# ESP32_BDB-2.net
KiCad netlist of a schematic drawn in Altium Designer
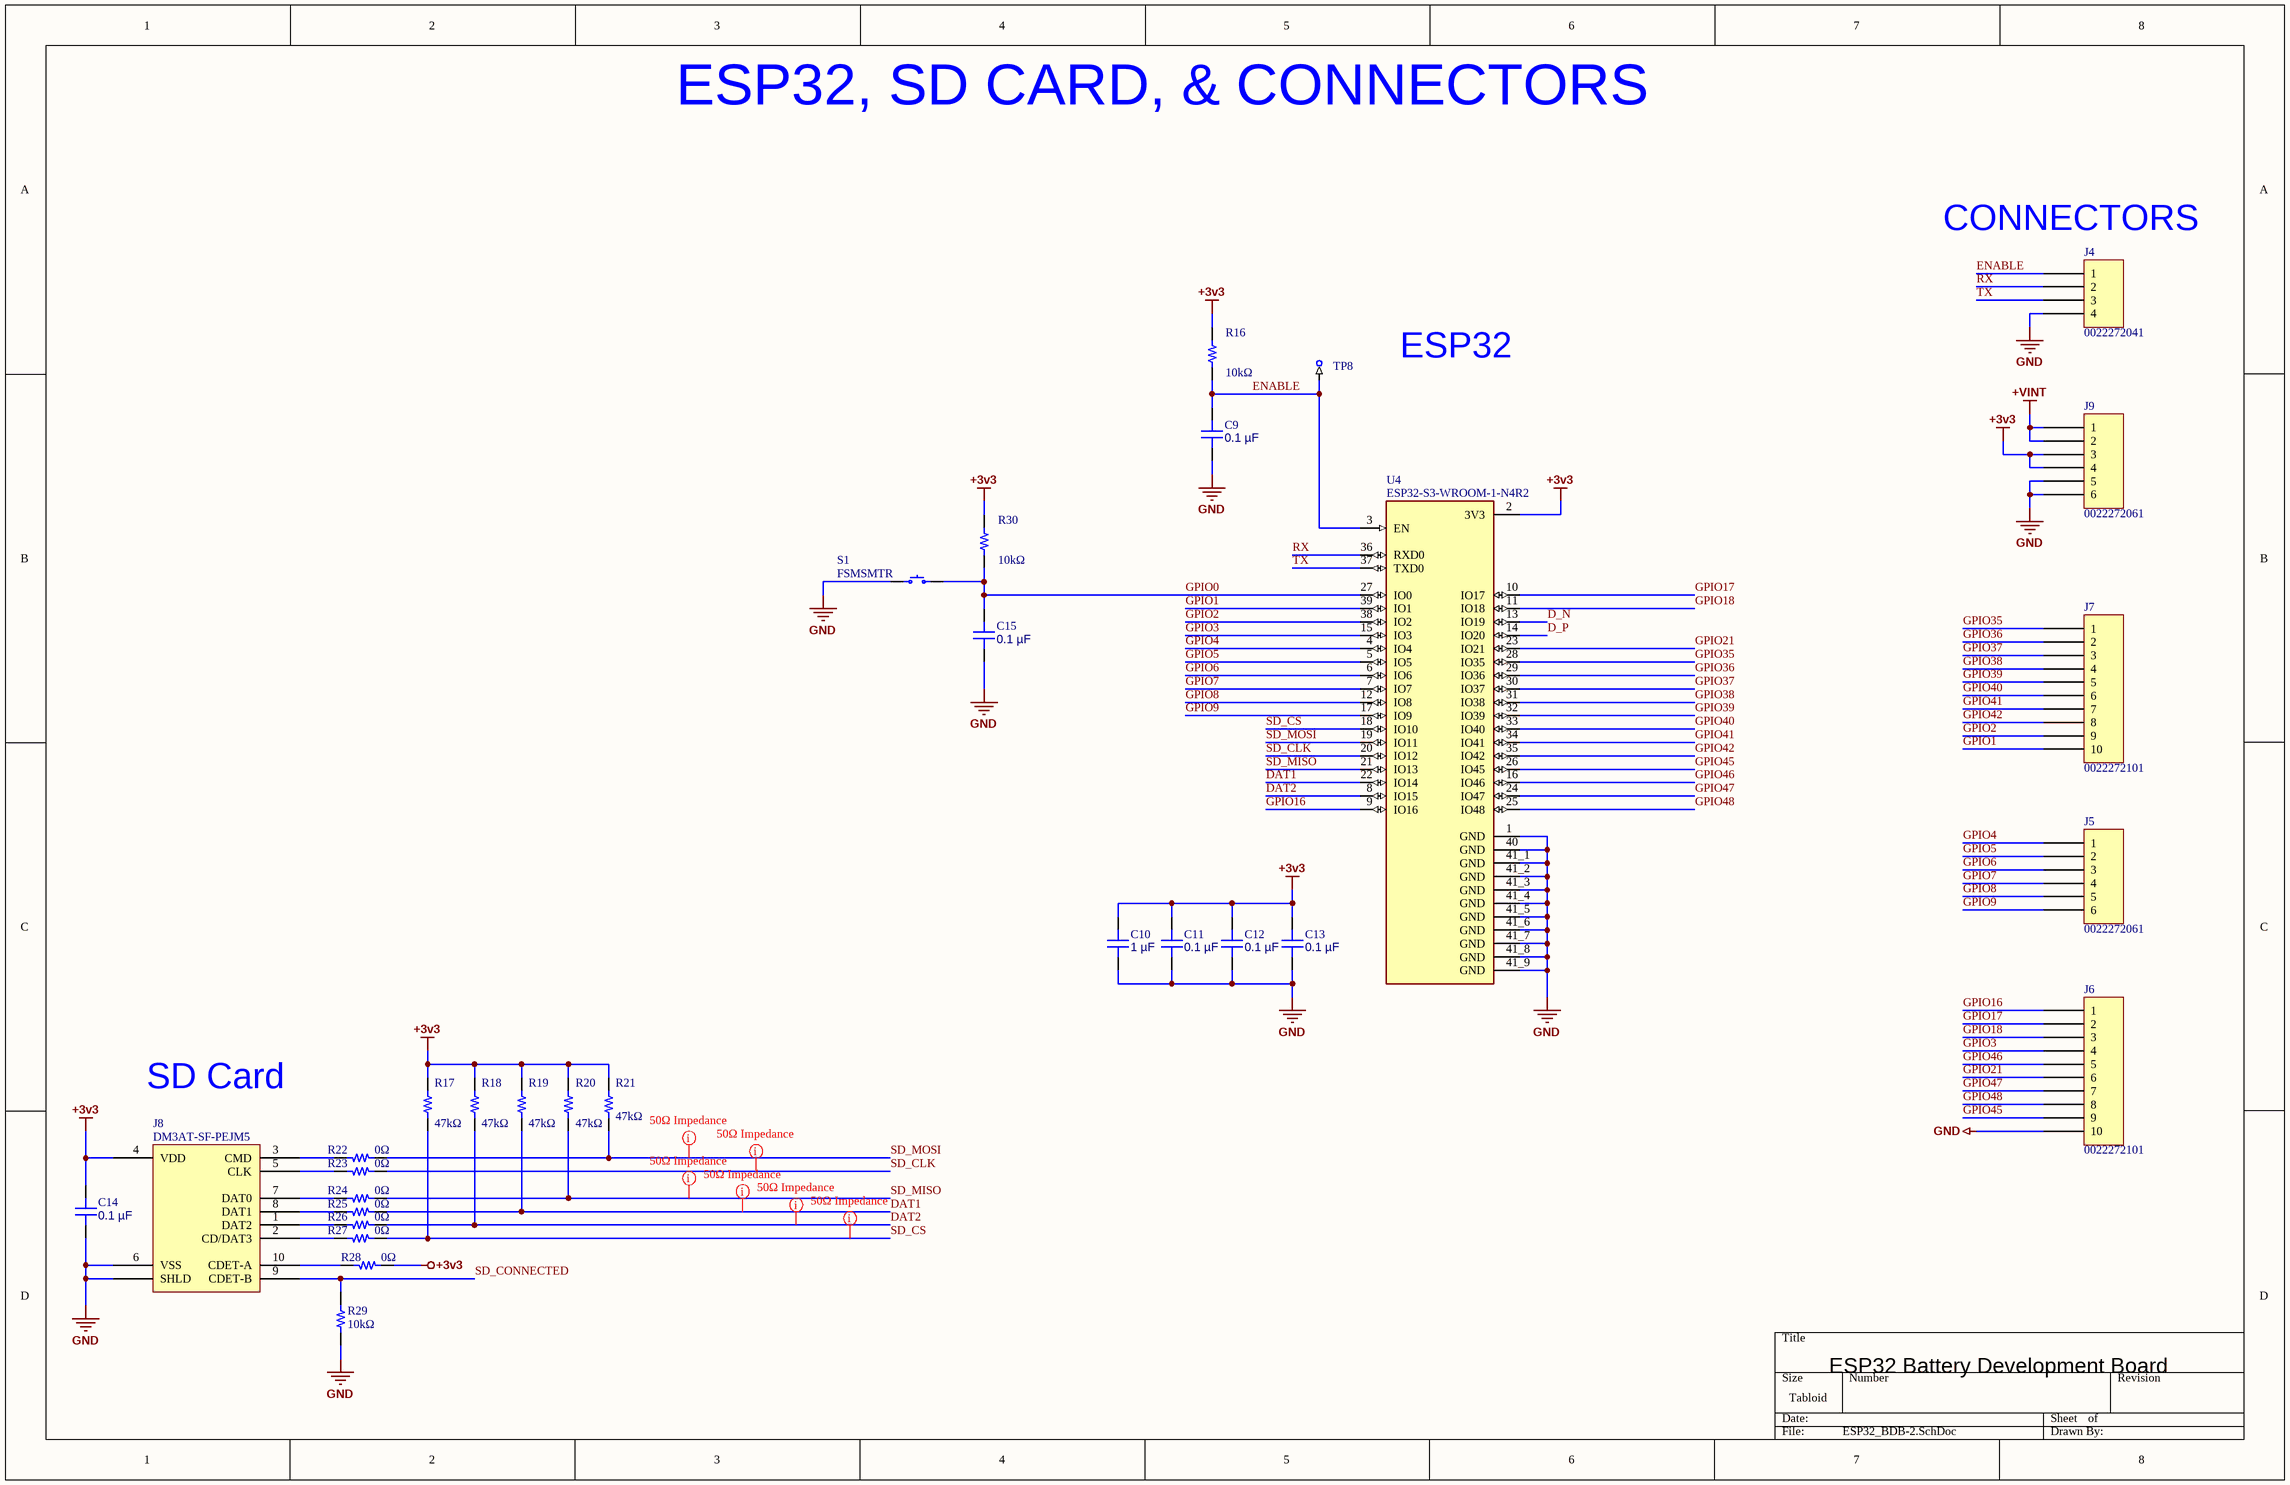
[diagram p0: ESP32_BDB-2.SchDoc]

(export (version "E")
  (design (tool "Eeschema 10.0.6"))
  (components
    (comp (ref "C9")
      (value "0.1 µF")
      (footprint "CAP 0603_1608")
      (description "CAP CER 0.1UF 50V X7R 0603")
      (fields
        (field (name "PART NUMBER") "C0603C104K5RAC7411")
        (field (name "CAPACITANCE") "0.1 µF")
        (field (name "MANUFACTURER") "KEMET")
      )
      (libsource (lib "Celestial Altium Library - altium_library") (part "Capacitor"))
    )
    (comp (ref "C10")
      (value "1 µF")
      (footprint "CAP 0603_1608")
      (description "CAP CER 1UF 10V X7R 0603")
      (fields
        (field (name "PART NUMBER") "CC0603KRX7R6BB105")
        (field (name "CAPACITANCE") "1 µF")
        (field (name "MANUFACTURER") "Yageo")
      )
      (libsource (lib "Celestial Altium Library - altium_library") (part "Capacitor"))
    )
    (comp (ref "C11")
      (value "0.1 µF")
      (footprint "CAP 0603_1608")
      (description "CAP CER 0.1UF 50V X7R 0603")
      (fields
        (field (name "PART NUMBER") "C0603C104K5RAC7411")
        (field (name "CAPACITANCE") "0.1 µF")
        (field (name "MANUFACTURER") "KEMET")
      )
      (libsource (lib "Celestial Altium Library - altium_library") (part "Capacitor"))
    )
    (comp (ref "C12")
      (value "0.1 µF")
      (footprint "CAP 0603_1608")
      (description "CAP CER 0.1UF 50V X7R 0603")
      (fields
        (field (name "PART NUMBER") "C0603C104K5RAC7411")
        (field (name "CAPACITANCE") "0.1 µF")
        (field (name "MANUFACTURER") "KEMET")
      )
      (libsource (lib "Celestial Altium Library - altium_library") (part "Capacitor"))
    )
    (comp (ref "C13")
      (value "0.1 µF")
      (footprint "CAP 0603_1608")
      (description "CAP CER 0.1UF 50V X7R 0603")
      (fields
        (field (name "PART NUMBER") "C0603C104K5RAC7411")
        (field (name "CAPACITANCE") "0.1 µF")
        (field (name "MANUFACTURER") "KEMET")
      )
      (libsource (lib "Celestial Altium Library - altium_library") (part "Capacitor"))
    )
    (comp (ref "C14")
      (value "0.1 µF")
      (footprint "CAP 0603_1608")
      (description "CAP CER 0.1UF 50V X7R 0603")
      (fields
        (field (name "PART NUMBER") "C0603C104K5RAC7411")
        (field (name "CAPACITANCE") "0.1 µF")
        (field (name "MANUFACTURER") "KEMET")
      )
      (libsource (lib "Celestial Altium Library - altium_library") (part "Capacitor"))
    )
    (comp (ref "C15")
      (value "0.1 µF")
      (footprint "CAP 0603_1608")
      (description "CAP CER 0.1UF 50V X7R 0603")
      (fields
        (field (name "PART NUMBER") "C0603C104K5RAC7411")
        (field (name "CAPACITANCE") "0.1 µF")
        (field (name "MANUFACTURER") "KEMET")
      )
      (libsource (lib "Celestial Altium Library - altium_library") (part "Capacitor"))
    )
    (comp (ref "J4")
      (value "0022272041")
      (footprint "MOLEX KK 0022272041")
      (description "CONN HEADER VERT 4POS 2.54MM")
      (fields (field (name "MANUFACTURER") "Molex"))
      (libsource (lib "Celestial Altium Library - altium_library") (part "4 Pin"))
    )
    (comp (ref "J5")
      (value "0022272061")
      (footprint "MOLEX KK 0022272061")
      (description "CONN HEADER VERT 6POS 2.54MM")
      (fields (field (name "MANUFACTURER") "Molex"))
      (libsource (lib "Celestial Altium Library - altium_library") (part "6 Pin"))
    )
    (comp (ref "J6")
      (value "0022272101")
      (footprint "MOLEX KK 0022272101")
      (description "CONN HEADER VERT 10POS 2.54MM")
      (fields (field (name "MANUFACTURER") "Molex"))
      (libsource (lib "Celestial Altium Library - altium_library") (part "10 Pin"))
    )
    (comp (ref "J7")
      (value "0022272101")
      (footprint "MOLEX KK 0022272101")
      (description "CONN HEADER VERT 10POS 2.54MM")
      (fields (field (name "MANUFACTURER") "Molex"))
      (libsource (lib "Celestial Altium Library - altium_library") (part "10 Pin"))
    )
    (comp (ref "J8")
      (value "DM3AT-SF-PEJM5")
      (footprint "HIROSE DM3AT-SF-PEJM5")
      (description "CONN MICRO SD CARD PUSH-PUSH R/A")
      (fields (field (name "MANUFACTURER") "Hirose Electric Co Ltd"))
      (libsource (lib "Celestial Altium Library - altium_library") (part "Hirose DM3 MicroSD"))
    )
    (comp (ref "J9")
      (value "0022272061")
      (footprint "MOLEX KK 0022272061")
      (description "CONN HEADER VERT 6POS 2.54MM")
      (fields (field (name "MANUFACTURER") "Molex"))
      (libsource (lib "Celestial Altium Library - altium_library") (part "6 Pin"))
    )
    (comp (ref "R16")
      (value "10kΩ")
      (footprint "RES 0603_1608")
      (description "RES SMD 10K OHM 1% 1/10W 0603")
      (fields (field (name "PART NUMBER") "AA0603FR-0710KL") (field (name "MANUFACTURER") "Yageo"))
      (libsource (lib "Celestial Altium Library - altium_library") (part "Resistor"))
    )
    (comp (ref "R17")
      (value "47kΩ")
      (footprint "RES 0603_1608")
      (description "RES SMD 47K OHM 1% 1/10W 0603")
      (fields (field (name "PART NUMBER") "AC0603FR-0747KL") (field (name "MANUFACTURER") "Yageo"))
      (libsource (lib "Celestial Altium Library - altium_library") (part "Resistor"))
    )
    (comp (ref "R18")
      (value "47kΩ")
      (footprint "RES 0603_1608")
      (description "RES SMD 47K OHM 1% 1/10W 0603")
      (fields (field (name "PART NUMBER") "AC0603FR-0747KL") (field (name "MANUFACTURER") "Yageo"))
      (libsource (lib "Celestial Altium Library - altium_library") (part "Resistor"))
    )
    (comp (ref "R19")
      (value "47kΩ")
      (footprint "RES 0603_1608")
      (description "RES SMD 47K OHM 1% 1/10W 0603")
      (fields (field (name "PART NUMBER") "AC0603FR-0747KL") (field (name "MANUFACTURER") "Yageo"))
      (libsource (lib "Celestial Altium Library - altium_library") (part "Resistor"))
    )
    (comp (ref "R20")
      (value "47kΩ")
      (footprint "RES 0603_1608")
      (description "RES SMD 47K OHM 1% 1/10W 0603")
      (fields (field (name "PART NUMBER") "AC0603FR-0747KL") (field (name "MANUFACTURER") "Yageo"))
      (libsource (lib "Celestial Altium Library - altium_library") (part "Resistor"))
    )
    (comp (ref "R21")
      (value "47kΩ")
      (footprint "RES 0603_1608")
      (description "RES SMD 47K OHM 1% 1/10W 0603")
      (fields (field (name "PART NUMBER") "AC0603FR-0747KL") (field (name "MANUFACTURER") "Yageo"))
      (libsource (lib "Celestial Altium Library - altium_library") (part "Resistor"))
    )
    (comp (ref "R22")
      (value "0Ω")
      (footprint "RES 0805_2012")
      (description "RES 0 OHM JUMPER 0805")
      (fields
        (field (name "PART NUMBER") "TLRZ2ATTD")
        (field (name "MANUFACTURER") "KOA Speer Electronics, Inc.")
      )
      (libsource (lib "Celestial Altium Library - altium_library") (part "Resistor"))
    )
    (comp (ref "R23")
      (value "0Ω")
      (footprint "RES 0805_2012")
      (description "RES 0 OHM JUMPER 0805")
      (fields
        (field (name "PART NUMBER") "TLRZ2ATTD")
        (field (name "MANUFACTURER") "KOA Speer Electronics, Inc.")
      )
      (libsource (lib "Celestial Altium Library - altium_library") (part "Resistor"))
    )
    (comp (ref "R24")
      (value "0Ω")
      (footprint "RES 0805_2012")
      (description "RES 0 OHM JUMPER 0805")
      (fields
        (field (name "PART NUMBER") "TLRZ2ATTD")
        (field (name "MANUFACTURER") "KOA Speer Electronics, Inc.")
      )
      (libsource (lib "Celestial Altium Library - altium_library") (part "Resistor"))
    )
    (comp (ref "R25")
      (value "0Ω")
      (footprint "RES 0805_2012")
      (description "RES 0 OHM JUMPER 0805")
      (fields
        (field (name "PART NUMBER") "TLRZ2ATTD")
        (field (name "MANUFACTURER") "KOA Speer Electronics, Inc.")
      )
      (libsource (lib "Celestial Altium Library - altium_library") (part "Resistor"))
    )
    (comp (ref "R26")
      (value "0Ω")
      (footprint "RES 0805_2012")
      (description "RES 0 OHM JUMPER 0805")
      (fields
        (field (name "PART NUMBER") "TLRZ2ATTD")
        (field (name "MANUFACTURER") "KOA Speer Electronics, Inc.")
      )
      (libsource (lib "Celestial Altium Library - altium_library") (part "Resistor"))
    )
    (comp (ref "R27")
      (value "0Ω")
      (footprint "RES 0805_2012")
      (description "RES 0 OHM JUMPER 0805")
      (fields
        (field (name "PART NUMBER") "TLRZ2ATTD")
        (field (name "MANUFACTURER") "KOA Speer Electronics, Inc.")
      )
      (libsource (lib "Celestial Altium Library - altium_library") (part "Resistor"))
    )
    (comp (ref "R28")
      (value "0Ω")
      (footprint "RES 0805_2012")
      (description "RES 0 OHM JUMPER 0805")
      (fields
        (field (name "PART NUMBER") "TLRZ2ATTD")
        (field (name "MANUFACTURER") "KOA Speer Electronics, Inc.")
      )
      (libsource (lib "Celestial Altium Library - altium_library") (part "Resistor"))
    )
    (comp (ref "R29")
      (value "10kΩ")
      (footprint "RES 0603_1608")
      (description "RES SMD 10K OHM 1% 1/10W 0603")
      (fields (field (name "PART NUMBER") "AA0603FR-0710KL") (field (name "MANUFACTURER") "Yageo"))
      (libsource (lib "Celestial Altium Library - altium_library") (part "Resistor"))
    )
    (comp (ref "R30")
      (value "10kΩ")
      (footprint "RES 0603_1608")
      (description "RES SMD 10K OHM 1% 1/10W 0603")
      (fields (field (name "PART NUMBER") "AA0603FR-0710KL") (field (name "MANUFACTURER") "Yageo"))
      (libsource (lib "Celestial Altium Library - altium_library") (part "Resistor"))
    )
    (comp (ref "S1")
      (value "FSMSMTR")
      (footprint "TE FSMSMTR")
      (description "SWITCH TACTILE SPST-NO 0.05A 24V")
      (fields (field (name "MANUFACTURER") "TE Connectivity ALCOSWITCH Switches"))
      (libsource (lib "Celestial Altium Library - altium_library") (part "SPST-NO 2 PIN"))
    )
    (comp (ref "TP8")
      (value "5016")
      (footprint "KEYSTONE-5016_V")
      (description "Test Point, 1-Pin SMT, RoHS, Tape and Reel")
      (fields (field (name "MANUFACTURER") "Keystone"))
      (libsource (lib "Altium Content Vault") (part "KEYSTONE-5016"))
    )
    (comp (ref "U4")
      (value "ESP32-S3-WROOM-1-N4R2")
      (footprint "XCVR_ESP32-S3-WROOM-1-N4R2")
      (description "Bluetooth, WiFi 802.11b/g/n, Bluetooth v5.0 Transceiver Module 2.4GHz PCB Trace Surface Mount")
      (fields (field (name "MF") "Espressif Systems"))
      (libsource (lib "ESP32-S3-WROOM-1-N4R2") (part "ESP32-S3-WROOM-1-N4R2"))
    )
  )
  (nets
    (net (code "1") (name "+3v3") (class "Default")
      (node (ref "C10") (pin "2") (pinfunction "2_2") (pintype "passive"))
      (node (ref "C11") (pin "2") (pinfunction "2_2") (pintype "passive"))
      (node (ref "C12") (pin "2") (pinfunction "2_2") (pintype "passive"))
      (node (ref "C13") (pin "2") (pinfunction "2_2") (pintype "passive"))
      (node (ref "C14") (pin "2") (pinfunction "2_2") (pintype "passive"))
      (node (ref "J8") (pin "4") (pinfunction "VDD_4") (pintype "passive"))
      (node (ref "J9") (pin "3") (pinfunction "3_3") (pintype "passive"))
      (node (ref "J9") (pin "4") (pinfunction "4_4") (pintype "passive"))
      (node (ref "R16") (pin "2") (pinfunction "2_2") (pintype "passive"))
      (node (ref "R17") (pin "2") (pinfunction "2_2") (pintype "passive"))
      (node (ref "R18") (pin "2") (pinfunction "2_2") (pintype "passive"))
      (node (ref "R19") (pin "2") (pinfunction "2_2") (pintype "passive"))
      (node (ref "R20") (pin "2") (pinfunction "2_2") (pintype "passive"))
      (node (ref "R21") (pin "2") (pinfunction "2_2") (pintype "passive"))
      (node (ref "R28") (pin "1") (pinfunction "1_1") (pintype "passive"))
      (node (ref "R30") (pin "2") (pinfunction "2_2") (pintype "passive"))
      (node (ref "U4") (pin "2") (pinfunction "3V3_2") (pintype "power_in"))
    )
    (net (code "2") (name "+VINT") (class "Default")
      (node (ref "J9") (pin "1") (pinfunction "1_1") (pintype "passive"))
      (node (ref "J9") (pin "2") (pinfunction "2_2") (pintype "passive"))
    )
    (net (code "3") (name "/DAT1") (class "Default")
      (node (ref "R19") (pin "1") (pinfunction "1_1") (pintype "passive"))
      (node (ref "R25") (pin "1") (pinfunction "1_1") (pintype "passive"))
      (node (ref "U4") (pin "22") (pinfunction "IO14_22") (pintype "bidirectional"))
    )
    (net (code "4") (name "/DAT2") (class "Default")
      (node (ref "R18") (pin "1") (pinfunction "1_1") (pintype "passive"))
      (node (ref "R26") (pin "1") (pinfunction "1_1") (pintype "passive"))
      (node (ref "U4") (pin "8") (pinfunction "IO15_8") (pintype "bidirectional"))
    )
    (net (code "5") (name "/D_N") (class "Default")
      (node (ref "U4") (pin "13") (pinfunction "IO19_13") (pintype "bidirectional"))
    )
    (net (code "6") (name "/D_P") (class "Default")
      (node (ref "U4") (pin "14") (pinfunction "IO20_14") (pintype "bidirectional"))
    )
    (net (code "7") (name "/ENABLE") (class "Default")
      (node (ref "C9") (pin "2") (pinfunction "2_2") (pintype "passive"))
      (node (ref "J4") (pin "1") (pinfunction "1_1") (pintype "passive"))
      (node (ref "R16") (pin "1") (pinfunction "1_1") (pintype "passive"))
      (node (ref "TP8") (pin "1") (pinfunction "1_1") (pintype "input"))
      (node (ref "U4") (pin "3") (pinfunction "EN_3") (pintype "input"))
    )
    (net (code "8") (name "/GPIO0") (class "Default")
      (node (ref "C15") (pin "2") (pinfunction "2_2") (pintype "passive"))
      (node (ref "R30") (pin "1") (pinfunction "1_1") (pintype "passive"))
      (node (ref "S1") (pin "2") (pinfunction "2_2") (pintype "passive"))
      (node (ref "U4") (pin "27") (pinfunction "IO0_27") (pintype "bidirectional"))
    )
    (net (code "9") (name "/GPIO1") (class "Default")
      (node (ref "J7") (pin "10") (pinfunction "10_10") (pintype "passive"))
      (node (ref "U4") (pin "39") (pinfunction "IO1_39") (pintype "bidirectional"))
    )
    (net (code "10") (name "/GPIO2") (class "Default")
      (node (ref "J7") (pin "9") (pinfunction "9_9") (pintype "passive"))
      (node (ref "U4") (pin "38") (pinfunction "IO2_38") (pintype "bidirectional"))
    )
    (net (code "11") (name "/GPIO3") (class "Default")
      (node (ref "J6") (pin "4") (pinfunction "4_4") (pintype "passive"))
      (node (ref "U4") (pin "15") (pinfunction "IO3_15") (pintype "bidirectional"))
    )
    (net (code "12") (name "/GPIO4") (class "Default")
      (node (ref "J5") (pin "1") (pinfunction "1_1") (pintype "passive"))
      (node (ref "U4") (pin "4") (pinfunction "IO4_4") (pintype "bidirectional"))
    )
    (net (code "13") (name "/GPIO5") (class "Default")
      (node (ref "J5") (pin "2") (pinfunction "2_2") (pintype "passive"))
      (node (ref "U4") (pin "5") (pinfunction "IO5_5") (pintype "bidirectional"))
    )
    (net (code "14") (name "/GPIO6") (class "Default")
      (node (ref "J5") (pin "3") (pinfunction "3_3") (pintype "passive"))
      (node (ref "U4") (pin "6") (pinfunction "IO6_6") (pintype "bidirectional"))
    )
    (net (code "15") (name "/GPIO7") (class "Default")
      (node (ref "J5") (pin "4") (pinfunction "4_4") (pintype "passive"))
      (node (ref "U4") (pin "7") (pinfunction "IO7_7") (pintype "bidirectional"))
    )
    (net (code "16") (name "/GPIO8") (class "Default")
      (node (ref "J5") (pin "5") (pinfunction "5_5") (pintype "passive"))
      (node (ref "U4") (pin "12") (pinfunction "IO8_12") (pintype "bidirectional"))
    )
    (net (code "17") (name "/GPIO9") (class "Default")
      (node (ref "J5") (pin "6") (pinfunction "6_6") (pintype "passive"))
      (node (ref "U4") (pin "17") (pinfunction "IO9_17") (pintype "bidirectional"))
    )
    (net (code "18") (name "/GPIO16") (class "Default")
      (node (ref "J6") (pin "1") (pinfunction "1_1") (pintype "passive"))
      (node (ref "U4") (pin "9") (pinfunction "IO16_9") (pintype "bidirectional"))
    )
    (net (code "19") (name "/GPIO17") (class "Default")
      (node (ref "J6") (pin "2") (pinfunction "2_2") (pintype "passive"))
      (node (ref "U4") (pin "10") (pinfunction "IO17_10") (pintype "bidirectional"))
    )
    (net (code "20") (name "/GPIO18") (class "Default")
      (node (ref "J6") (pin "3") (pinfunction "3_3") (pintype "passive"))
      (node (ref "U4") (pin "11") (pinfunction "IO18_11") (pintype "bidirectional"))
    )
    (net (code "21") (name "/GPIO21") (class "Default")
      (node (ref "J6") (pin "6") (pinfunction "6_6") (pintype "passive"))
      (node (ref "U4") (pin "23") (pinfunction "IO21_23") (pintype "bidirectional"))
    )
    (net (code "22") (name "/GPIO35") (class "Default")
      (node (ref "J7") (pin "1") (pinfunction "1_1") (pintype "passive"))
      (node (ref "U4") (pin "28") (pinfunction "IO35_28") (pintype "bidirectional"))
    )
    (net (code "23") (name "/GPIO36") (class "Default")
      (node (ref "J7") (pin "2") (pinfunction "2_2") (pintype "passive"))
      (node (ref "U4") (pin "29") (pinfunction "IO36_29") (pintype "bidirectional"))
    )
    (net (code "24") (name "/GPIO37") (class "Default")
      (node (ref "J7") (pin "3") (pinfunction "3_3") (pintype "passive"))
      (node (ref "U4") (pin "30") (pinfunction "IO37_30") (pintype "bidirectional"))
    )
    (net (code "25") (name "/GPIO38") (class "Default")
      (node (ref "J7") (pin "4") (pinfunction "4_4") (pintype "passive"))
      (node (ref "U4") (pin "31") (pinfunction "IO38_31") (pintype "bidirectional"))
    )
    (net (code "26") (name "/GPIO39") (class "Default")
      (node (ref "J7") (pin "5") (pinfunction "5_5") (pintype "passive"))
      (node (ref "U4") (pin "32") (pinfunction "IO39_32") (pintype "bidirectional"))
    )
    (net (code "27") (name "/GPIO40") (class "Default")
      (node (ref "J7") (pin "6") (pinfunction "6_6") (pintype "passive"))
      (node (ref "U4") (pin "33") (pinfunction "IO40_33") (pintype "bidirectional"))
    )
    (net (code "28") (name "/GPIO41") (class "Default")
      (node (ref "J7") (pin "7") (pinfunction "7_7") (pintype "passive"))
      (node (ref "U4") (pin "34") (pinfunction "IO41_34") (pintype "bidirectional"))
    )
    (net (code "29") (name "/GPIO42") (class "Default")
      (node (ref "J7") (pin "8") (pinfunction "8_8") (pintype "passive"))
      (node (ref "U4") (pin "35") (pinfunction "IO42_35") (pintype "bidirectional"))
    )
    (net (code "30") (name "/GPIO45") (class "Default")
      (node (ref "J6") (pin "9") (pinfunction "9_9") (pintype "passive"))
      (node (ref "U4") (pin "26") (pinfunction "IO45_26") (pintype "bidirectional"))
    )
    (net (code "31") (name "/GPIO46") (class "Default")
      (node (ref "J6") (pin "5") (pinfunction "5_5") (pintype "passive"))
      (node (ref "U4") (pin "16") (pinfunction "IO46_16") (pintype "bidirectional"))
    )
    (net (code "32") (name "/GPIO47") (class "Default")
      (node (ref "J6") (pin "7") (pinfunction "7_7") (pintype "passive"))
      (node (ref "U4") (pin "24") (pinfunction "IO47_24") (pintype "bidirectional"))
    )
    (net (code "33") (name "/GPIO48") (class "Default")
      (node (ref "J6") (pin "8") (pinfunction "8_8") (pintype "passive"))
      (node (ref "U4") (pin "25") (pinfunction "IO48_25") (pintype "bidirectional"))
    )
    (net (code "34") (name "/RX") (class "Default")
      (node (ref "J4") (pin "2") (pinfunction "2_2") (pintype "passive"))
      (node (ref "U4") (pin "36") (pinfunction "RXD0_36") (pintype "bidirectional"))
    )
    (net (code "35") (name "/SD_CLK") (class "Default")
      (node (ref "R23") (pin "1") (pinfunction "1_1") (pintype "passive"))
      (node (ref "U4") (pin "20") (pinfunction "IO12_20") (pintype "bidirectional"))
    )
    (net (code "36") (name "/SD_CONNECTED") (class "Default")
      (node (ref "J8") (pin "9") (pinfunction "CDET-B_9") (pintype "passive"))
      (node (ref "R29") (pin "2") (pinfunction "2_2") (pintype "passive"))
    )
    (net (code "37") (name "/SD_CS") (class "Default")
      (node (ref "R17") (pin "1") (pinfunction "1_1") (pintype "passive"))
      (node (ref "R27") (pin "1") (pinfunction "1_1") (pintype "passive"))
      (node (ref "U4") (pin "18") (pinfunction "IO10_18") (pintype "bidirectional"))
    )
    (net (code "38") (name "/SD_MISO") (class "Default")
      (node (ref "R20") (pin "1") (pinfunction "1_1") (pintype "passive"))
      (node (ref "R24") (pin "1") (pinfunction "1_1") (pintype "passive"))
      (node (ref "U4") (pin "21") (pinfunction "IO13_21") (pintype "bidirectional"))
    )
    (net (code "39") (name "/SD_MOSI") (class "Default")
      (node (ref "R21") (pin "1") (pinfunction "1_1") (pintype "passive"))
      (node (ref "R22") (pin "1") (pinfunction "1_1") (pintype "passive"))
      (node (ref "U4") (pin "19") (pinfunction "IO11_19") (pintype "bidirectional"))
    )
    (net (code "40") (name "/TX") (class "Default")
      (node (ref "J4") (pin "3") (pinfunction "3_3") (pintype "passive"))
      (node (ref "U4") (pin "37") (pinfunction "TXD0_37") (pintype "bidirectional"))
    )
    (net (code "41") (name "GND") (class "Default")
      (node (ref "C10") (pin "1") (pinfunction "1_1") (pintype "passive"))
      (node (ref "C11") (pin "1") (pinfunction "1_1") (pintype "passive"))
      (node (ref "C12") (pin "1") (pinfunction "1_1") (pintype "passive"))
      (node (ref "C13") (pin "1") (pinfunction "1_1") (pintype "passive"))
      (node (ref "C14") (pin "1") (pinfunction "1_1") (pintype "passive"))
      (node (ref "C15") (pin "1") (pinfunction "1_1") (pintype "passive"))
      (node (ref "C9") (pin "1") (pinfunction "1_1") (pintype "passive"))
      (node (ref "J4") (pin "4") (pinfunction "4_4") (pintype "passive"))
      (node (ref "J6") (pin "10") (pinfunction "10_10") (pintype "passive"))
      (node (ref "J8") (pin "6") (pinfunction "VSS_6") (pintype "passive"))
      (node (ref "J8") (pin "S") (pinfunction "SHLD_S") (pintype "passive"))
      (node (ref "J9") (pin "5") (pinfunction "5_5") (pintype "passive"))
      (node (ref "J9") (pin "6") (pinfunction "6_6") (pintype "passive"))
      (node (ref "R29") (pin "1") (pinfunction "1_1") (pintype "passive"))
      (node (ref "S1") (pin "1") (pinfunction "1_1") (pintype "passive"))
      (node (ref "U4") (pin "1") (pinfunction "GND_1") (pintype "power_in"))
      (node (ref "U4") (pin "40") (pinfunction "GND_40") (pintype "power_in"))
      (node (ref "U4") (pin "41_1") (pinfunction "GND_41_1") (pintype "power_in"))
      (node (ref "U4") (pin "41_2") (pinfunction "GND_41_2") (pintype "power_in"))
      (node (ref "U4") (pin "41_3") (pinfunction "GND_41_3") (pintype "power_in"))
      (node (ref "U4") (pin "41_4") (pinfunction "GND_41_4") (pintype "power_in"))
      (node (ref "U4") (pin "41_5") (pinfunction "GND_41_5") (pintype "power_in"))
      (node (ref "U4") (pin "41_6") (pinfunction "GND_41_6") (pintype "power_in"))
      (node (ref "U4") (pin "41_7") (pinfunction "GND_41_7") (pintype "power_in"))
      (node (ref "U4") (pin "41_8") (pinfunction "GND_41_8") (pintype "power_in"))
      (node (ref "U4") (pin "41_9") (pinfunction "GND_41_9") (pintype "power_in"))
    )
    (net (code "42") (name "Net-(J8-CDET-A)") (class "Default")
      (node (ref "J8") (pin "10") (pinfunction "CDET-A_10") (pintype "passive"))
      (node (ref "R28") (pin "2") (pinfunction "2_2") (pintype "passive"))
    )
    (net (code "43") (name "Net-(J8-CD{slash}DAT3)") (class "Default")
      (node (ref "J8") (pin "2") (pinfunction "CD/DAT3_2") (pintype "passive"))
      (node (ref "R27") (pin "2") (pinfunction "2_2") (pintype "passive"))
    )
    (net (code "44") (name "Net-(J8-CLK)") (class "Default")
      (node (ref "J8") (pin "5") (pinfunction "CLK_5") (pintype "passive"))
      (node (ref "R23") (pin "2") (pinfunction "2_2") (pintype "passive"))
    )
    (net (code "45") (name "Net-(J8-CMD)") (class "Default")
      (node (ref "J8") (pin "3") (pinfunction "CMD_3") (pintype "passive"))
      (node (ref "R22") (pin "2") (pinfunction "2_2") (pintype "passive"))
    )
    (net (code "46") (name "Net-(J8-DAT0)") (class "Default")
      (node (ref "J8") (pin "7") (pinfunction "DAT0_7") (pintype "passive"))
      (node (ref "R24") (pin "2") (pinfunction "2_2") (pintype "passive"))
    )
    (net (code "47") (name "Net-(J8-DAT1)") (class "Default")
      (node (ref "J8") (pin "8") (pinfunction "DAT1_8") (pintype "passive"))
      (node (ref "R25") (pin "2") (pinfunction "2_2") (pintype "passive"))
    )
    (net (code "48") (name "Net-(J8-DAT2)") (class "Default")
      (node (ref "J8") (pin "1") (pinfunction "DAT2_1") (pintype "passive"))
      (node (ref "R26") (pin "2") (pinfunction "2_2") (pintype "passive"))
    )
  )
)
